# ESP32.net
KiCad netlist of a schematic drawn in EAGLE
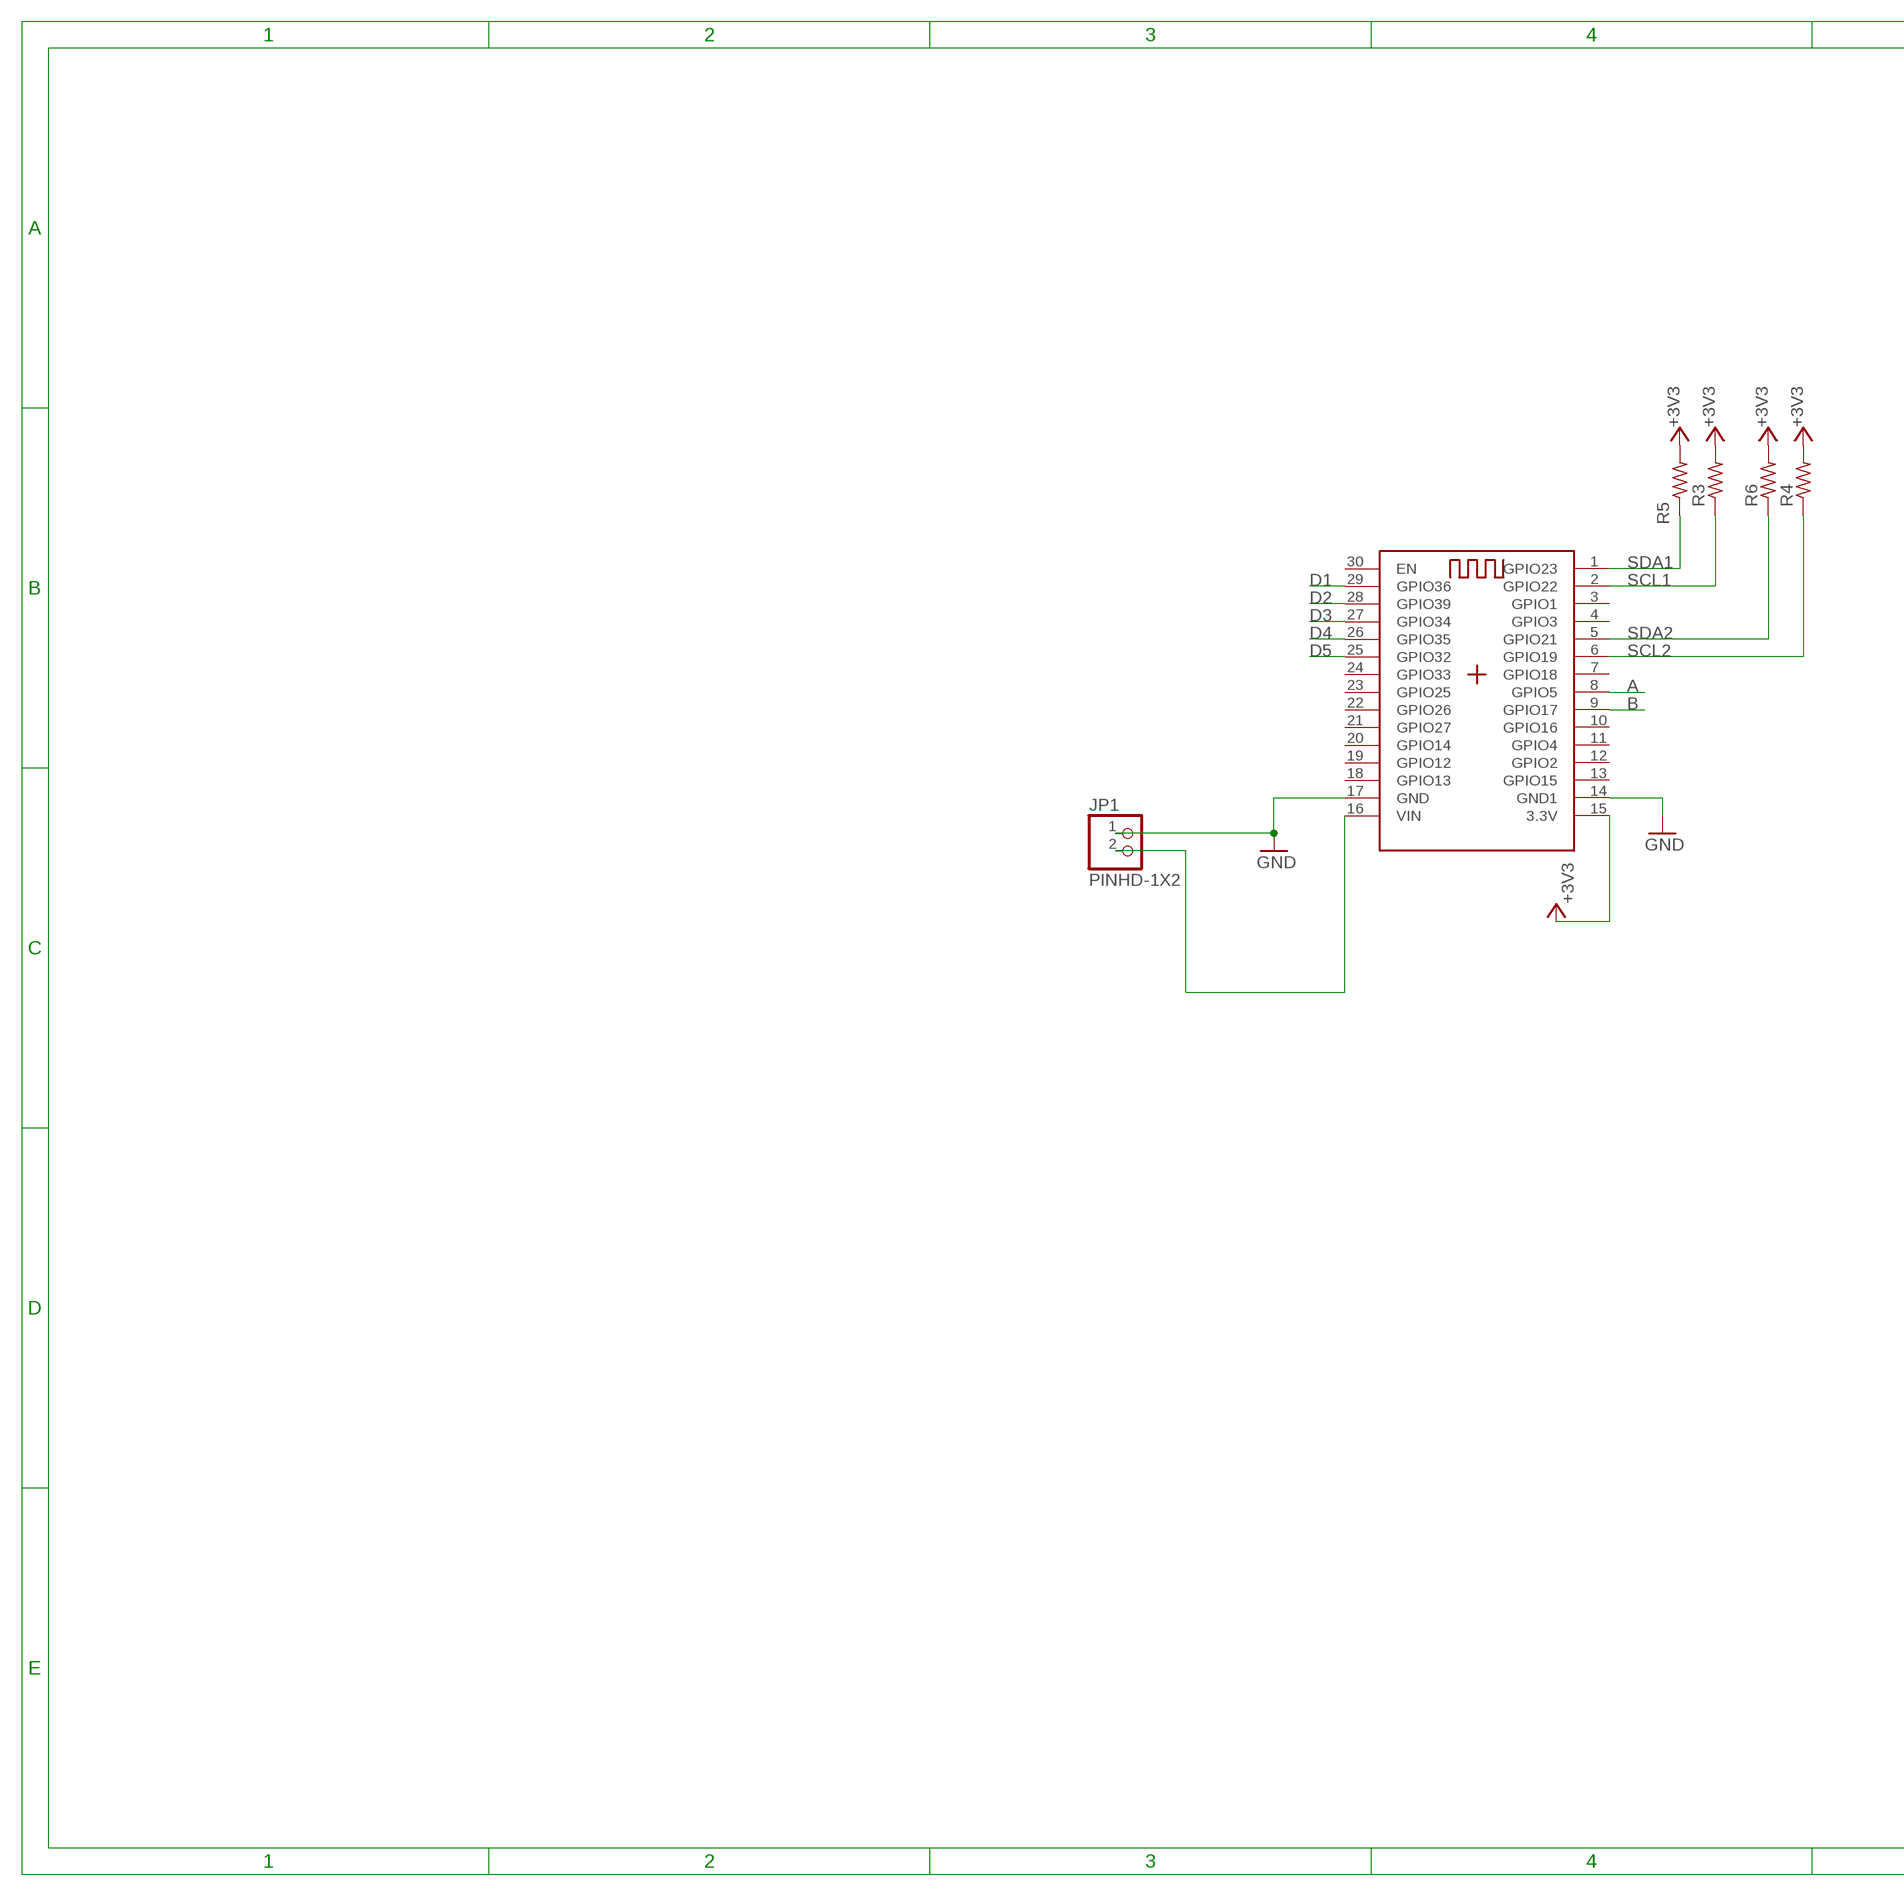
[diagram p0: schematic, sheet 1, part 1 of 2]
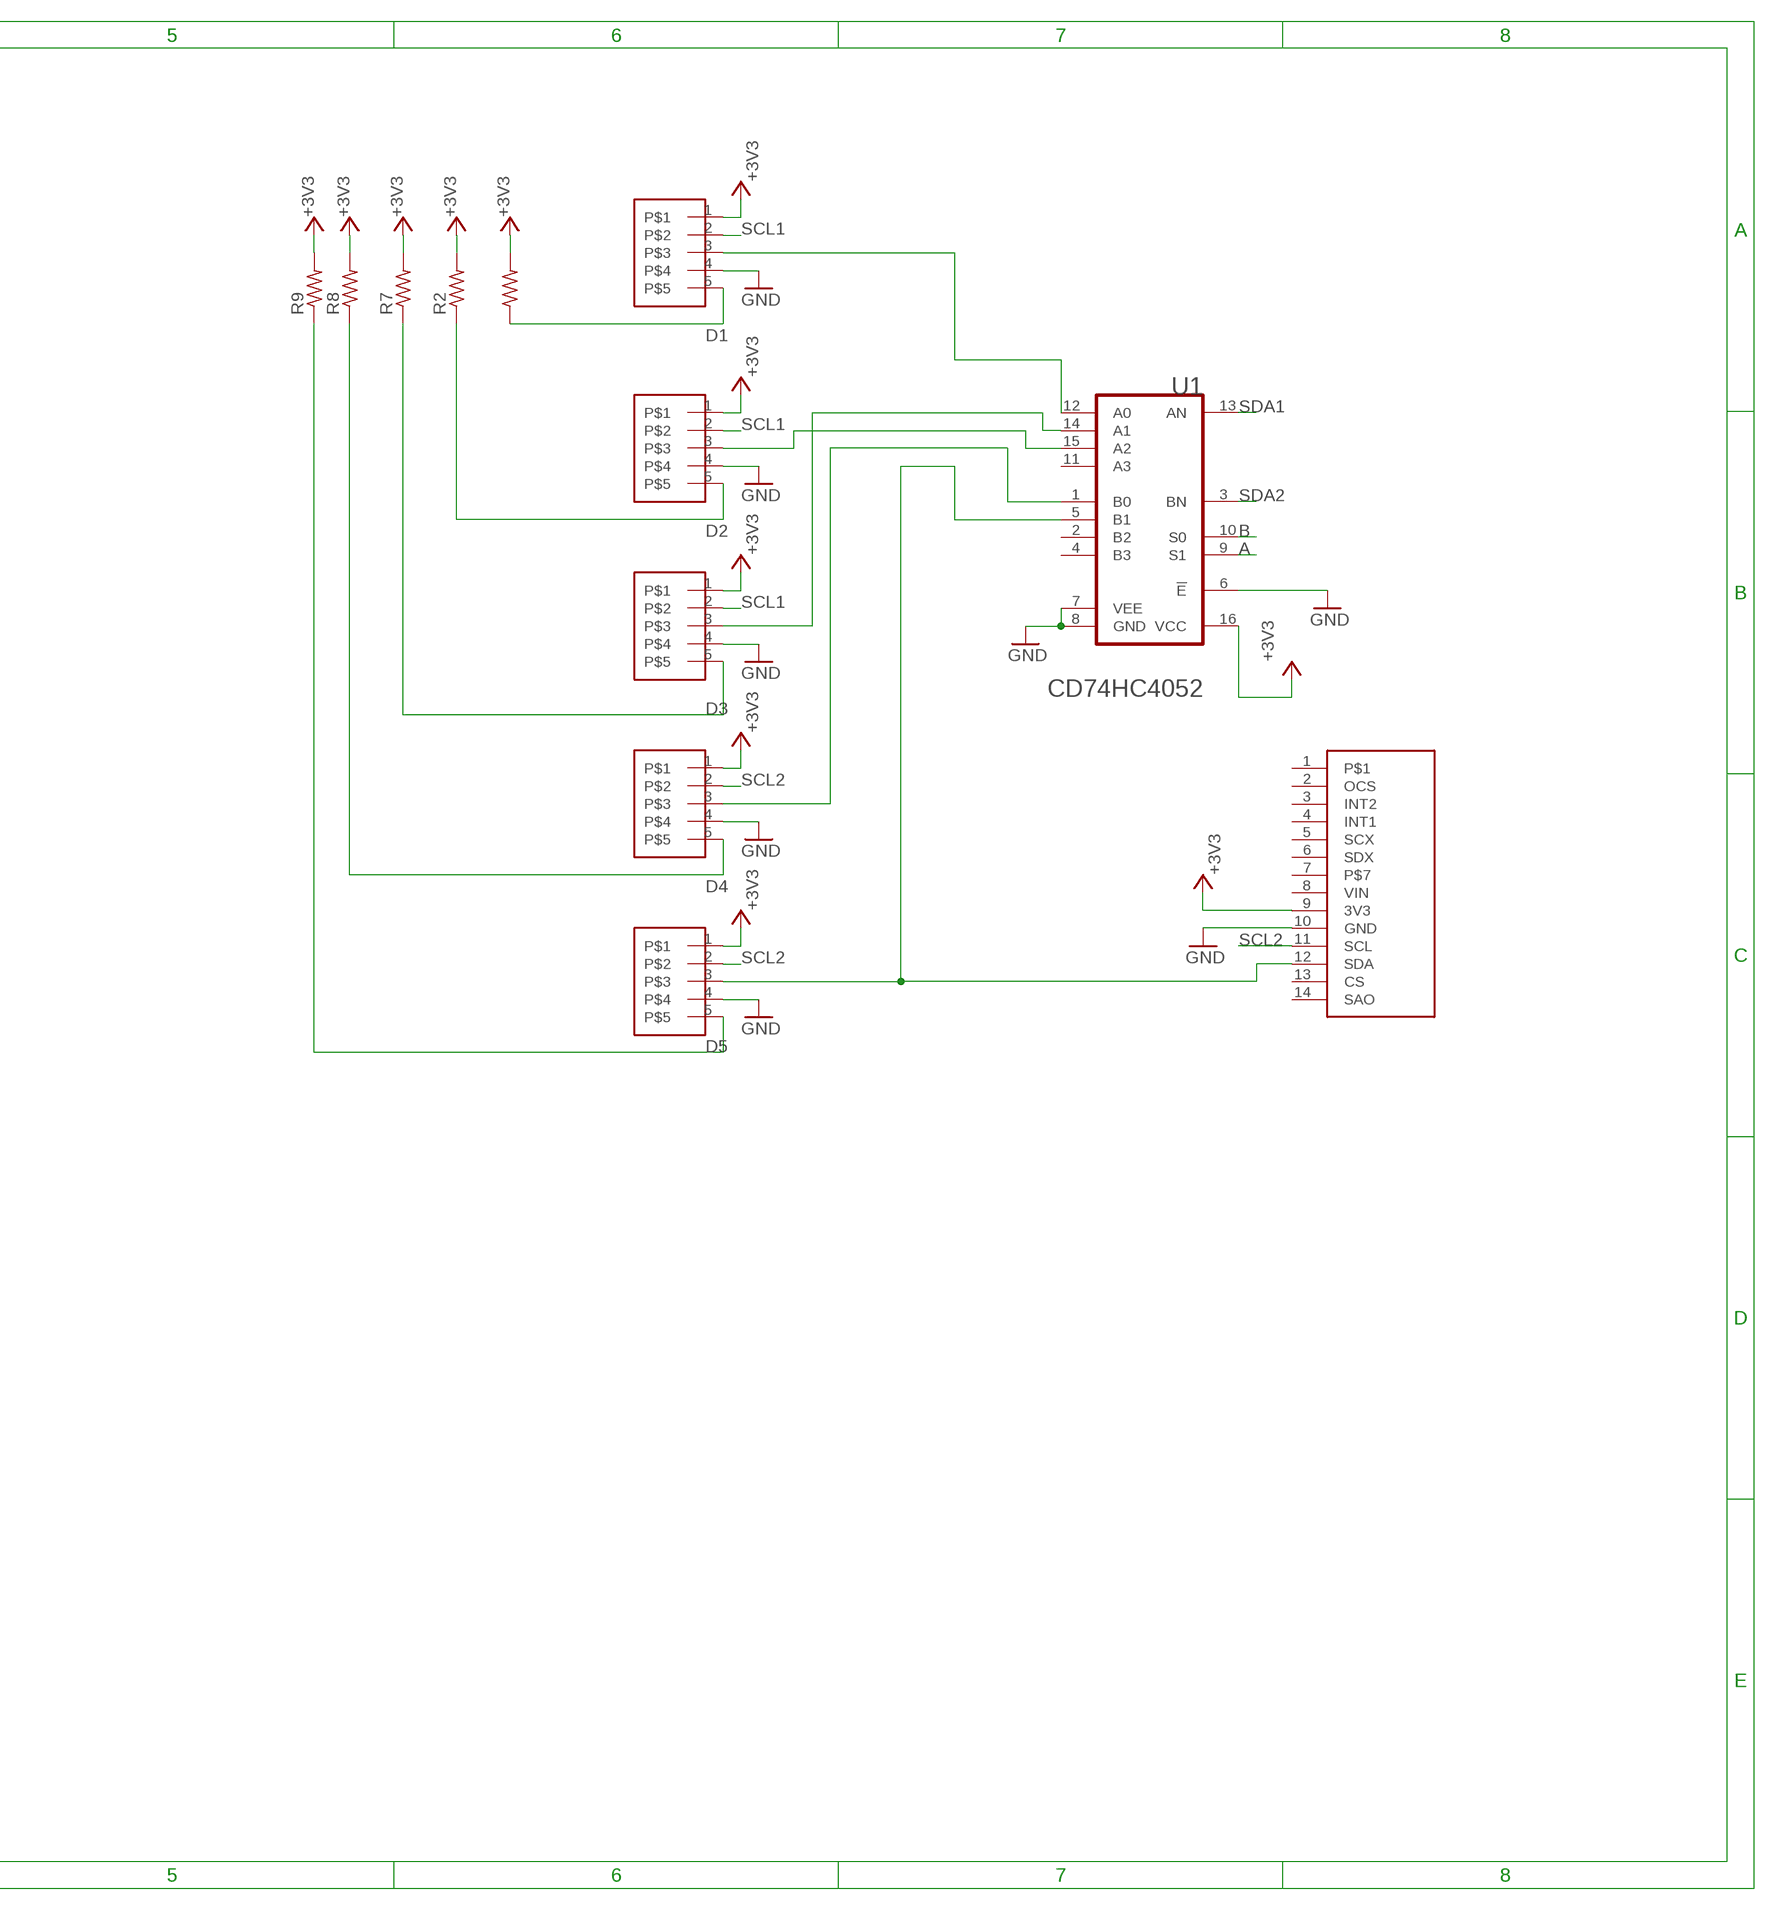
[diagram p1: schematic, sheet 1, part 2 of 2]

(export (version "E")
  (design (tool "Eeschema 10.0.6"))
  (components
    (comp (ref "JP1")
      (value "PINHD-1X2")
      (footprint "eagle-import:1X02")
      (libsource (lib "eagle-import") (part "PINHD-1X2"))
    )
    (comp (ref "R1")
      (value "10 khom")
      (footprint "eagle-import:RES_0805")
      (fields
        (field (name "DIGIKEY_PART_NUMBER") "541-0.0ATR-ND")
        (field (name "MANUFACTURER") "Vishay Dale")
        (field (name "MPN") "CRCW08050000Z0EA")
        (field (name "CREATED_BY") "PCBLayout.com")
      )
      (libsource (lib "eagle-import") (part "CRCW08050000Z0EA"))
    )
    (comp (ref "R2")
      (value "10 khom")
      (footprint "eagle-import:RES_0805")
      (fields
        (field (name "DIGIKEY_PART_NUMBER") "541-0.0ATR-ND")
        (field (name "MANUFACTURER") "Vishay Dale")
        (field (name "MPN") "CRCW08050000Z0EA")
        (field (name "CREATED_BY") "PCBLayout.com")
      )
      (libsource (lib "eagle-import") (part "CRCW08050000Z0EA"))
    )
    (comp (ref "R3")
      (value "10 kohm")
      (footprint "eagle-import:RES_0805")
      (fields
        (field (name "DIGIKEY_PART_NUMBER") "541-0.0ATR-ND")
        (field (name "MANUFACTURER") "Vishay Dale")
        (field (name "MPN") "CRCW08050000Z0EA")
        (field (name "CREATED_BY") "PCBLayout.com")
      )
      (libsource (lib "eagle-import") (part "CRCW08050000Z0EA"))
    )
    (comp (ref "R4")
      (value "10 kohm")
      (footprint "eagle-import:RES_0805")
      (fields
        (field (name "DIGIKEY_PART_NUMBER") "541-0.0ATR-ND")
        (field (name "MANUFACTURER") "Vishay Dale")
        (field (name "MPN") "CRCW08050000Z0EA")
        (field (name "CREATED_BY") "PCBLayout.com")
      )
      (libsource (lib "eagle-import") (part "CRCW08050000Z0EA"))
    )
    (comp (ref "R5")
      (value "10 khom")
      (footprint "eagle-import:RES_0805")
      (fields
        (field (name "DIGIKEY_PART_NUMBER") "541-0.0ATR-ND")
        (field (name "MANUFACTURER") "Vishay Dale")
        (field (name "MPN") "CRCW08050000Z0EA")
        (field (name "CREATED_BY") "PCBLayout.com")
      )
      (libsource (lib "eagle-import") (part "CRCW08050000Z0EA"))
    )
    (comp (ref "R6")
      (value "10 khom")
      (footprint "eagle-import:RES_0805")
      (fields
        (field (name "DIGIKEY_PART_NUMBER") "541-0.0ATR-ND")
        (field (name "MANUFACTURER") "Vishay Dale")
        (field (name "MPN") "CRCW08050000Z0EA")
        (field (name "CREATED_BY") "PCBLayout.com")
      )
      (libsource (lib "eagle-import") (part "CRCW08050000Z0EA"))
    )
    (comp (ref "R7")
      (value "10 khom")
      (footprint "eagle-import:RES_0805")
      (fields
        (field (name "DIGIKEY_PART_NUMBER") "541-0.0ATR-ND")
        (field (name "MANUFACTURER") "Vishay Dale")
        (field (name "MPN") "CRCW08050000Z0EA")
        (field (name "CREATED_BY") "PCBLayout.com")
      )
      (libsource (lib "eagle-import") (part "CRCW08050000Z0EA"))
    )
    (comp (ref "R8")
      (value "10 khom")
      (footprint "eagle-import:RES_0805")
      (fields
        (field (name "DIGIKEY_PART_NUMBER") "541-0.0ATR-ND")
        (field (name "MANUFACTURER") "Vishay Dale")
        (field (name "MPN") "CRCW08050000Z0EA")
        (field (name "CREATED_BY") "PCBLayout.com")
      )
      (libsource (lib "eagle-import") (part "CRCW08050000Z0EA"))
    )
    (comp (ref "R9")
      (value "10 khom")
      (footprint "eagle-import:RES_0805")
      (fields
        (field (name "DIGIKEY_PART_NUMBER") "541-0.0ATR-ND")
        (field (name "MANUFACTURER") "Vishay Dale")
        (field (name "MPN") "CRCW08050000Z0EA")
        (field (name "CREATED_BY") "PCBLayout.com")
      )
      (libsource (lib "eagle-import") (part "CRCW08050000Z0EA"))
    )
    (comp (ref "U$1")
      (value "ESP32ESP32")
      (footprint "eagle-import:HDRVR30W70P2540X254_2X15_4572X2794X254B")
      (libsource (lib "eagle-import") (part "ESP32ESP32"))
    )
    (comp (ref "U$3")
      (value "BMI160-MODULEBMI160-MODULE")
      (footprint "eagle-import:HDRV14W64P1016X254_2X7_1800X1300X838B")
      (libsource (lib "eagle-import") (part "BMI160-MODULEBMI160-MODULE"))
    )
    (comp (ref "U$8")
      (value "PHMN4-5PHMN4-51")
      (footprint "eagle-import:HDRRA5W70P200_1X5_1200X254X556B")
      (libsource (lib "eagle-import") (part "PHMN4-5PHMN4-51"))
    )
    (comp (ref "U$9")
      (value "PHMN4-5PHMN4-51")
      (footprint "eagle-import:HDRRA5W70P200_1X5_1200X254X556B")
      (libsource (lib "eagle-import") (part "PHMN4-5PHMN4-51"))
    )
    (comp (ref "U$10")
      (value "PHMN4-5PHMN4-51")
      (footprint "eagle-import:HDRRA5W70P200_1X5_1200X254X556B")
      (libsource (lib "eagle-import") (part "PHMN4-5PHMN4-51"))
    )
    (comp (ref "U$11")
      (value "PHMN4-5PHMN4-51")
      (footprint "eagle-import:HDRRA5W70P200_1X5_1200X254X556B")
      (libsource (lib "eagle-import") (part "PHMN4-5PHMN4-51"))
    )
    (comp (ref "U$12")
      (value "PHMN4-5PHMN4-51")
      (footprint "eagle-import:HDRRA5W70P200_1X5_1200X254X556B")
      (libsource (lib "eagle-import") (part "PHMN4-5PHMN4-51"))
    )
    (comp (ref "U1")
      (value "TEXAS_INSTRUMENTS_CD74HC4052TEXAS_INSTRUMENTS_CD74HC4052_0_0")
      (footprint "eagle-import:TEXAS_INSTRUMENTS_CD74HC4052_0")
      (fields (field (name "MF") "Texas Instruments") (field (name "MPN") "CD74HC4052"))
      (libsource (lib "eagle-import") (part "TEXAS_INSTRUMENTS_CD74HC4052TEXAS_INSTRUMENTS_CD74HC4052_0_0"))
    )
  )
  (nets
    (net (code "1") (name "+3V3") (class "Default")
      (node (ref "R1") (pin "2") (pinfunction "2_2") (pintype "passive"))
      (node (ref "R2") (pin "2") (pinfunction "2_2") (pintype "passive"))
      (node (ref "R3") (pin "2") (pinfunction "2_2") (pintype "passive"))
      (node (ref "R4") (pin "2") (pinfunction "2_2") (pintype "passive"))
      (node (ref "R5") (pin "2") (pinfunction "2_2") (pintype "passive"))
      (node (ref "R6") (pin "2") (pinfunction "2_2") (pintype "passive"))
      (node (ref "R7") (pin "2") (pinfunction "2_2") (pintype "passive"))
      (node (ref "R8") (pin "2") (pinfunction "2_2") (pintype "passive"))
      (node (ref "R9") (pin "2") (pinfunction "2_2") (pintype "passive"))
      (node (ref "U$1") (pin "15") (pinfunction "3.3V_15") (pintype "bidirectional"))
      (node (ref "U$10") (pin "1") (pinfunction "P$1_1") (pintype "bidirectional"))
      (node (ref "U$11") (pin "1") (pinfunction "P$1_1") (pintype "bidirectional"))
      (node (ref "U$12") (pin "1") (pinfunction "P$1_1") (pintype "bidirectional"))
      (node (ref "U$3") (pin "9") (pinfunction "3V3_9") (pintype "bidirectional"))
      (node (ref "U$8") (pin "1") (pinfunction "P$1_1") (pintype "bidirectional"))
      (node (ref "U$9") (pin "1") (pinfunction "P$1_1") (pintype "bidirectional"))
      (node (ref "U1") (pin "16") (pinfunction "VCC_16") (pintype "power_in"))
    )
    (net (code "2") (name "/A") (class "Default")
      (node (ref "U$1") (pin "8") (pinfunction "GPIO5_8") (pintype "bidirectional"))
      (node (ref "U1") (pin "9") (pinfunction "S1_9") (pintype "input"))
    )
    (net (code "3") (name "/B") (class "Default")
      (node (ref "U$1") (pin "9") (pinfunction "GPIO17_9") (pintype "bidirectional"))
      (node (ref "U1") (pin "10") (pinfunction "S0_10") (pintype "input"))
    )
    (net (code "4") (name "/D1") (class "Default")
      (node (ref "R1") (pin "1") (pinfunction "1_1") (pintype "passive"))
      (node (ref "U$1") (pin "29") (pinfunction "GPIO36_29") (pintype "bidirectional"))
      (node (ref "U$8") (pin "5") (pinfunction "P$5_5") (pintype "bidirectional"))
    )
    (net (code "5") (name "/D2") (class "Default")
      (node (ref "R2") (pin "1") (pinfunction "1_1") (pintype "passive"))
      (node (ref "U$1") (pin "28") (pinfunction "GPIO39_28") (pintype "bidirectional"))
      (node (ref "U$9") (pin "5") (pinfunction "P$5_5") (pintype "bidirectional"))
    )
    (net (code "6") (name "/D3") (class "Default")
      (node (ref "R7") (pin "1") (pinfunction "1_1") (pintype "passive"))
      (node (ref "U$1") (pin "27") (pinfunction "GPIO34_27") (pintype "bidirectional"))
      (node (ref "U$10") (pin "5") (pinfunction "P$5_5") (pintype "bidirectional"))
    )
    (net (code "7") (name "/D4") (class "Default")
      (node (ref "R8") (pin "1") (pinfunction "1_1") (pintype "passive"))
      (node (ref "U$1") (pin "26") (pinfunction "GPIO35_26") (pintype "bidirectional"))
      (node (ref "U$11") (pin "5") (pinfunction "P$5_5") (pintype "bidirectional"))
    )
    (net (code "8") (name "/D5") (class "Default")
      (node (ref "R9") (pin "1") (pinfunction "1_1") (pintype "passive"))
      (node (ref "U$1") (pin "25") (pinfunction "GPIO32_25") (pintype "bidirectional"))
      (node (ref "U$12") (pin "5") (pinfunction "P$5_5") (pintype "bidirectional"))
    )
    (net (code "9") (name "/SCL1") (class "Default")
      (node (ref "R3") (pin "1") (pinfunction "1_1") (pintype "passive"))
      (node (ref "U$1") (pin "2") (pinfunction "GPIO22_2") (pintype "bidirectional"))
      (node (ref "U$10") (pin "2") (pinfunction "P$2_2") (pintype "bidirectional"))
      (node (ref "U$8") (pin "2") (pinfunction "P$2_2") (pintype "bidirectional"))
      (node (ref "U$9") (pin "2") (pinfunction "P$2_2") (pintype "bidirectional"))
    )
    (net (code "10") (name "/SCL2") (class "Default")
      (node (ref "R4") (pin "1") (pinfunction "1_1") (pintype "passive"))
      (node (ref "U$1") (pin "6") (pinfunction "GPIO19_6") (pintype "bidirectional"))
      (node (ref "U$11") (pin "2") (pinfunction "P$2_2") (pintype "bidirectional"))
      (node (ref "U$12") (pin "2") (pinfunction "P$2_2") (pintype "bidirectional"))
      (node (ref "U$3") (pin "11") (pinfunction "SCL_11") (pintype "bidirectional"))
    )
    (net (code "11") (name "/SDA1") (class "Default")
      (node (ref "R5") (pin "1") (pinfunction "1_1") (pintype "passive"))
      (node (ref "U$1") (pin "1") (pinfunction "GPIO23_1") (pintype "bidirectional"))
      (node (ref "U1") (pin "13") (pinfunction "AN_13") (pintype "passive"))
    )
    (net (code "12") (name "/SDA2") (class "Default")
      (node (ref "R6") (pin "1") (pinfunction "1_1") (pintype "passive"))
      (node (ref "U$1") (pin "5") (pinfunction "GPIO21_5") (pintype "bidirectional"))
      (node (ref "U1") (pin "3") (pinfunction "BN_3") (pintype "passive"))
    )
    (net (code "13") (name "GND") (class "Default")
      (node (ref "JP1") (pin "1") (pinfunction "1_1") (pintype "passive"))
      (node (ref "U$1") (pin "14") (pinfunction "GND1_14") (pintype "bidirectional"))
      (node (ref "U$1") (pin "17") (pinfunction "GND_17") (pintype "bidirectional"))
      (node (ref "U$10") (pin "4") (pinfunction "P$4_4") (pintype "bidirectional"))
      (node (ref "U$11") (pin "4") (pinfunction "P$4_4") (pintype "bidirectional"))
      (node (ref "U$12") (pin "4") (pinfunction "P$4_4") (pintype "bidirectional"))
      (node (ref "U$3") (pin "10") (pinfunction "GND_10") (pintype "bidirectional"))
      (node (ref "U$8") (pin "4") (pinfunction "P$4_4") (pintype "bidirectional"))
      (node (ref "U$9") (pin "4") (pinfunction "P$4_4") (pintype "bidirectional"))
      (node (ref "U1") (pin "6") (pinfunction "~{E}_6") (pintype "input"))
      (node (ref "U1") (pin "7") (pinfunction "VEE_7") (pintype "power_in"))
      (node (ref "U1") (pin "8") (pinfunction "GND_8") (pintype "power_in"))
    )
    (net (code "14") (name "Net-(U$1-VIN)") (class "Default")
      (node (ref "JP1") (pin "2") (pinfunction "2_2") (pintype "passive"))
      (node (ref "U$1") (pin "16") (pinfunction "VIN_16") (pintype "bidirectional"))
    )
    (net (code "15") (name "Net-(U$8-P$3)") (class "Default")
      (node (ref "U$8") (pin "3") (pinfunction "P$3_3") (pintype "bidirectional"))
      (node (ref "U1") (pin "12") (pinfunction "A0_12") (pintype "passive"))
    )
    (net (code "16") (name "Net-(U$9-P$3)") (class "Default")
      (node (ref "U$9") (pin "3") (pinfunction "P$3_3") (pintype "bidirectional"))
      (node (ref "U1") (pin "15") (pinfunction "A2_15") (pintype "passive"))
    )
    (net (code "17") (name "Net-(U$10-P$3)") (class "Default")
      (node (ref "U$10") (pin "3") (pinfunction "P$3_3") (pintype "bidirectional"))
      (node (ref "U1") (pin "14") (pinfunction "A1_14") (pintype "passive"))
    )
    (net (code "18") (name "Net-(U$11-P$3)") (class "Default")
      (node (ref "U$11") (pin "3") (pinfunction "P$3_3") (pintype "bidirectional"))
      (node (ref "U1") (pin "1") (pinfunction "B0_1") (pintype "passive"))
    )
    (net (code "19") (name "Net-(U$12-P$3)") (class "Default")
      (node (ref "U$12") (pin "3") (pinfunction "P$3_3") (pintype "bidirectional"))
      (node (ref "U$3") (pin "12") (pinfunction "SDA_12") (pintype "bidirectional"))
      (node (ref "U1") (pin "5") (pinfunction "B1_5") (pintype "passive"))
    )
    (net (code "20") (name "unconnected-(U$1-EN-Pad30)") (class "Default")
      (node (ref "U$1") (pin "30") (pinfunction "EN_30") (pintype "bidirectional"))
    )
    (net (code "21") (name "unconnected-(U$1-GPIO1-Pad3)") (class "Default")
      (node (ref "U$1") (pin "3") (pinfunction "GPIO1_3") (pintype "bidirectional"))
    )
    (net (code "22") (name "unconnected-(U$1-GPIO2-Pad12)") (class "Default")
      (node (ref "U$1") (pin "12") (pinfunction "GPIO2_12") (pintype "bidirectional"))
    )
    (net (code "23") (name "unconnected-(U$1-GPIO3-Pad4)") (class "Default")
      (node (ref "U$1") (pin "4") (pinfunction "GPIO3_4") (pintype "bidirectional"))
    )
    (net (code "24") (name "unconnected-(U$1-GPIO4-Pad11)") (class "Default")
      (node (ref "U$1") (pin "11") (pinfunction "GPIO4_11") (pintype "bidirectional"))
    )
    (net (code "25") (name "unconnected-(U$1-GPIO12-Pad19)") (class "Default")
      (node (ref "U$1") (pin "19") (pinfunction "GPIO12_19") (pintype "bidirectional"))
    )
    (net (code "26") (name "unconnected-(U$1-GPIO13-Pad18)") (class "Default")
      (node (ref "U$1") (pin "18") (pinfunction "GPIO13_18") (pintype "bidirectional"))
    )
    (net (code "27") (name "unconnected-(U$1-GPIO14-Pad20)") (class "Default")
      (node (ref "U$1") (pin "20") (pinfunction "GPIO14_20") (pintype "bidirectional"))
    )
    (net (code "28") (name "unconnected-(U$1-GPIO15-Pad13)") (class "Default")
      (node (ref "U$1") (pin "13") (pinfunction "GPIO15_13") (pintype "bidirectional"))
    )
    (net (code "29") (name "unconnected-(U$1-GPIO16-Pad10)") (class "Default")
      (node (ref "U$1") (pin "10") (pinfunction "GPIO16_10") (pintype "bidirectional"))
    )
    (net (code "30") (name "unconnected-(U$1-GPIO18-Pad7)") (class "Default")
      (node (ref "U$1") (pin "7") (pinfunction "GPIO18_7") (pintype "bidirectional"))
    )
    (net (code "31") (name "unconnected-(U$1-GPIO25-Pad23)") (class "Default")
      (node (ref "U$1") (pin "23") (pinfunction "GPIO25_23") (pintype "bidirectional"))
    )
    (net (code "32") (name "unconnected-(U$1-GPIO26-Pad22)") (class "Default")
      (node (ref "U$1") (pin "22") (pinfunction "GPIO26_22") (pintype "bidirectional"))
    )
    (net (code "33") (name "unconnected-(U$1-GPIO27-Pad21)") (class "Default")
      (node (ref "U$1") (pin "21") (pinfunction "GPIO27_21") (pintype "bidirectional"))
    )
    (net (code "34") (name "unconnected-(U$1-GPIO33-Pad24)") (class "Default")
      (node (ref "U$1") (pin "24") (pinfunction "GPIO33_24") (pintype "bidirectional"))
    )
    (net (code "35") (name "unconnected-(U$3-CS-Pad13)") (class "Default")
      (node (ref "U$3") (pin "13") (pinfunction "CS_13") (pintype "bidirectional"))
    )
    (net (code "36") (name "unconnected-(U$3-INT1-Pad4)") (class "Default")
      (node (ref "U$3") (pin "4") (pinfunction "INT1_4") (pintype "bidirectional"))
    )
    (net (code "37") (name "unconnected-(U$3-INT2-Pad3)") (class "Default")
      (node (ref "U$3") (pin "3") (pinfunction "INT2_3") (pintype "bidirectional"))
    )
    (net (code "38") (name "unconnected-(U$3-OCS-Pad2)") (class "Default")
      (node (ref "U$3") (pin "2") (pinfunction "OCS_2") (pintype "bidirectional"))
    )
    (net (code "39") (name "unconnected-(U$3-P$1-Pad1)") (class "Default")
      (node (ref "U$3") (pin "1") (pinfunction "P$1_1") (pintype "bidirectional"))
    )
    (net (code "40") (name "unconnected-(U$3-P$7-Pad7)") (class "Default")
      (node (ref "U$3") (pin "7") (pinfunction "P$7_7") (pintype "bidirectional"))
    )
    (net (code "41") (name "unconnected-(U$3-SAO-Pad14)") (class "Default")
      (node (ref "U$3") (pin "14") (pinfunction "SAO_14") (pintype "bidirectional"))
    )
    (net (code "42") (name "unconnected-(U$3-SCX-Pad5)") (class "Default")
      (node (ref "U$3") (pin "5") (pinfunction "SCX_5") (pintype "bidirectional"))
    )
    (net (code "43") (name "unconnected-(U$3-SDX-Pad6)") (class "Default")
      (node (ref "U$3") (pin "6") (pinfunction "SDX_6") (pintype "bidirectional"))
    )
    (net (code "44") (name "unconnected-(U$3-VIN-Pad8)") (class "Default")
      (node (ref "U$3") (pin "8") (pinfunction "VIN_8") (pintype "bidirectional"))
    )
    (net (code "45") (name "unconnected-(U1-A3-Pad11)") (class "Default")
      (node (ref "U1") (pin "11") (pinfunction "A3_11") (pintype "passive"))
    )
    (net (code "46") (name "unconnected-(U1-B2-Pad2)") (class "Default")
      (node (ref "U1") (pin "2") (pinfunction "B2_2") (pintype "passive"))
    )
    (net (code "47") (name "unconnected-(U1-B3-Pad4)") (class "Default")
      (node (ref "U1") (pin "4") (pinfunction "B3_4") (pintype "passive"))
    )
  )
)
